# Get_In_Line_REV0.net
KiCad netlist of a schematic drawn in EAGLE
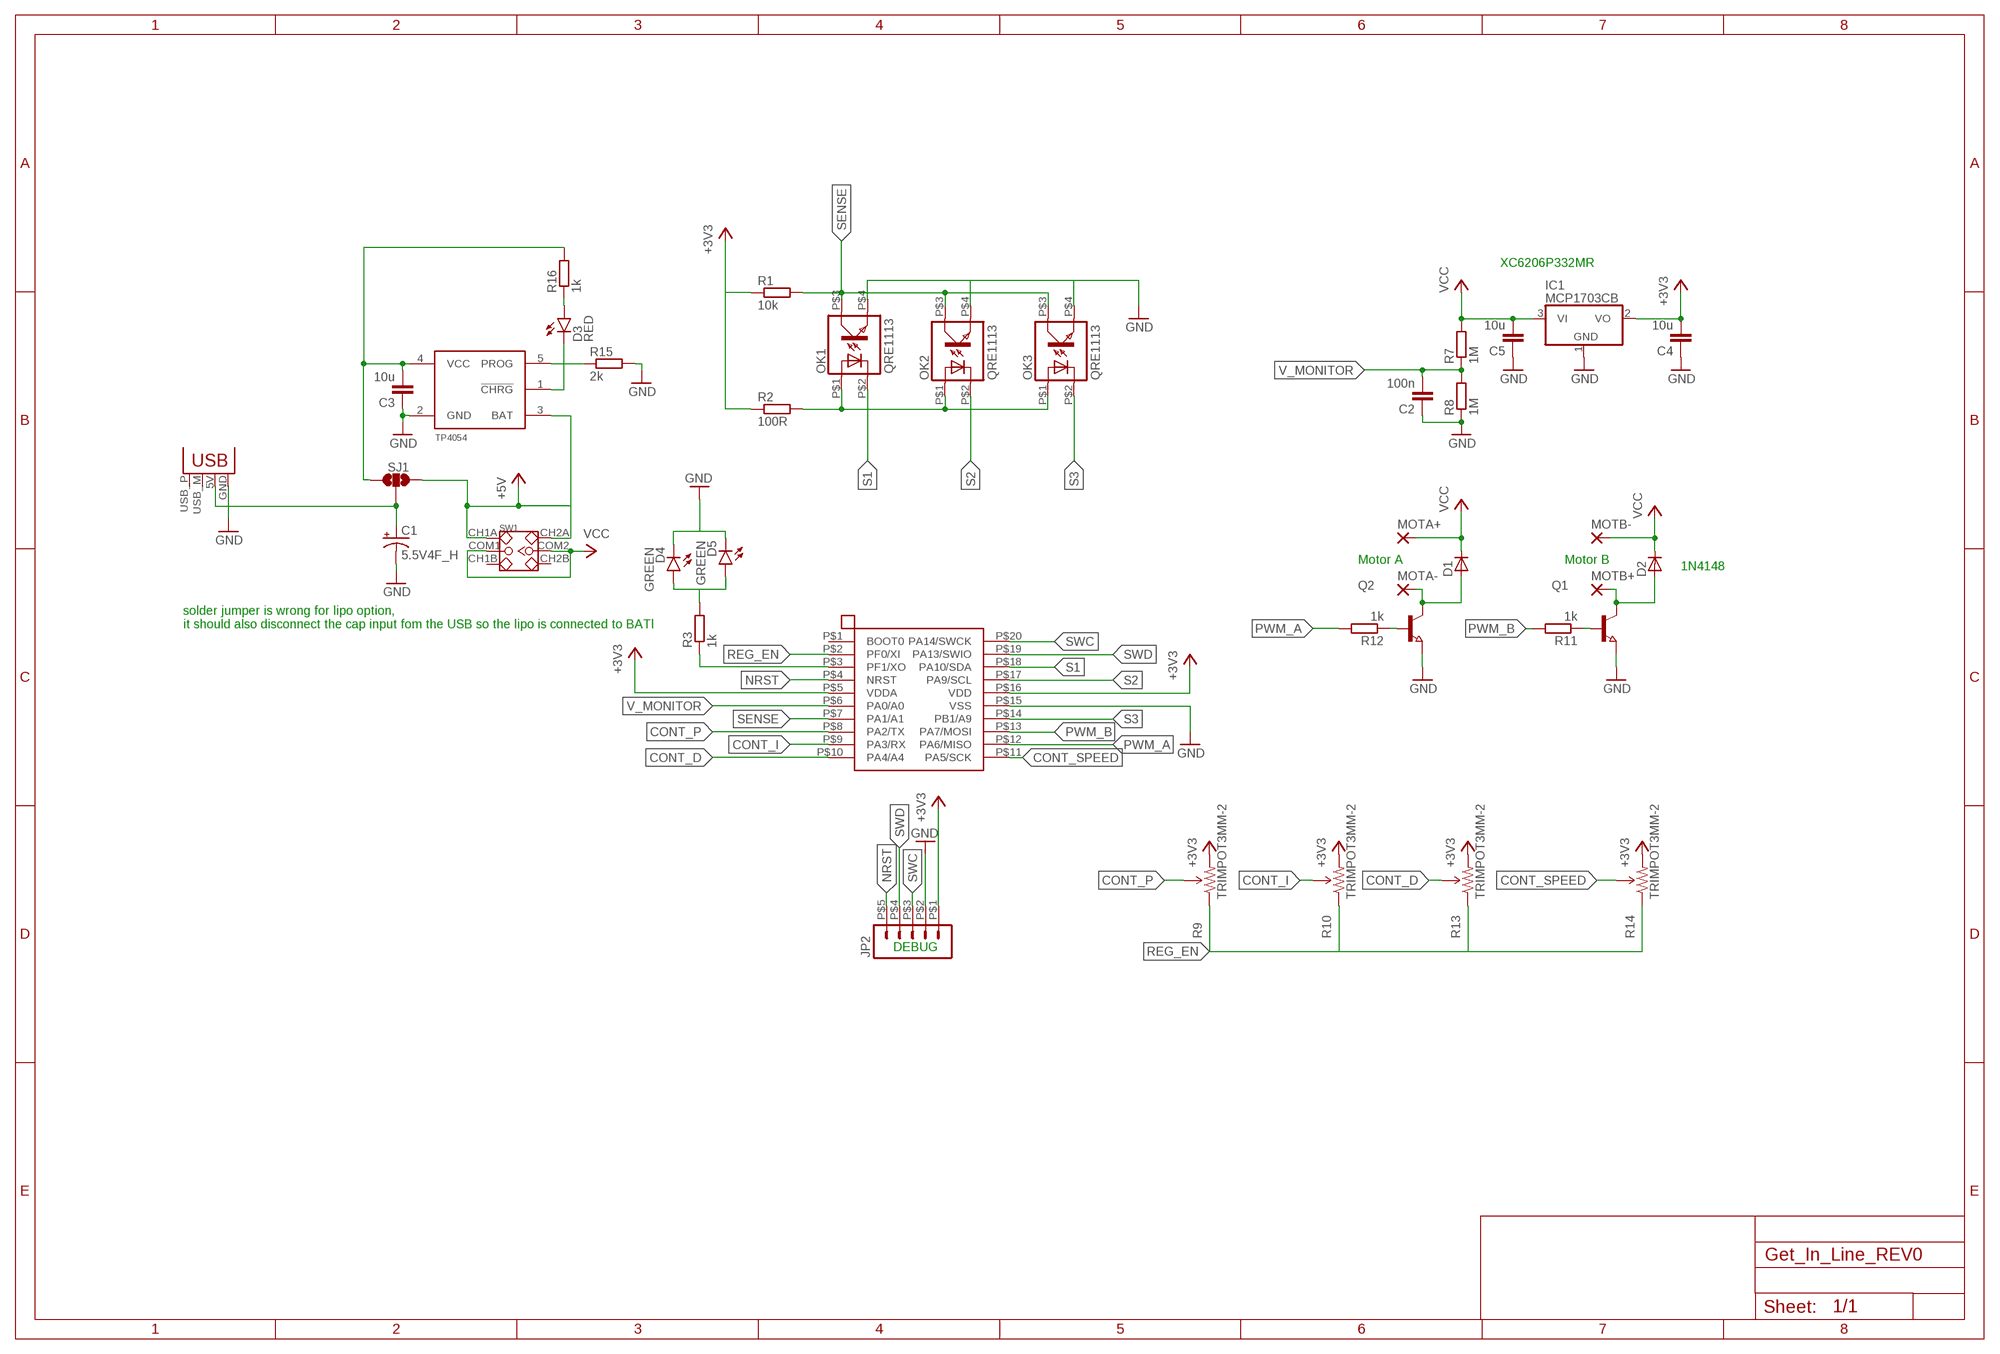
[diagram p0: schematic, sheet 1]

(export (version "E")
  (design (tool "Eeschema 10.0.6"))
  (components
    (comp (ref "C1")
      (value "5.5V4F_H")
      (footprint "eagle-import:5.5V4F_H")
      (libsource (lib "eagle-import") (part "5.5V4F_H"))
    )
    (comp (ref "C2")
      (value "100n")
      (footprint "eagle-import:C0805")
      (libsource (lib "eagle-import") (part "C-EUC0805"))
    )
    (comp (ref "C3")
      (value "10u")
      (footprint "eagle-import:C0805")
      (libsource (lib "eagle-import") (part "C-EUC0805"))
    )
    (comp (ref "C4")
      (value "10u")
      (footprint "eagle-import:C0805")
      (libsource (lib "eagle-import") (part "C-EUC0805"))
    )
    (comp (ref "C5")
      (value "10u")
      (footprint "eagle-import:C0805")
      (libsource (lib "eagle-import") (part "C-EUC0805"))
    )
    (comp (ref "D1")
      (value "D-SOD-80")
      (footprint "eagle-import:SOD80")
      (libsource (lib "eagle-import") (part "D-SOD-80"))
    )
    (comp (ref "D2")
      (value "D-SOD-80")
      (footprint "eagle-import:SOD80")
      (libsource (lib "eagle-import") (part "D-SOD-80"))
    )
    (comp (ref "D3")
      (value "RED")
      (footprint "eagle-import:LED-1206")
      (libsource (lib "eagle-import") (part "LED-RED1206"))
    )
    (comp (ref "D4")
      (value "GREEN")
      (footprint "eagle-import:LED-1206")
      (libsource (lib "eagle-import") (part "LED-GREENLARGE"))
    )
    (comp (ref "D5")
      (value "GREEN")
      (footprint "eagle-import:LED-1206")
      (libsource (lib "eagle-import") (part "LED-GREENLARGE"))
    )
    (comp (ref "IC1")
      (value "MCP1703CB")
      (footprint "eagle-import:SOT23")
      (libsource (lib "eagle-import") (part "MCP1703CB"))
    )
    (comp (ref "JP1")
      (value "USBPCB")
      (footprint "eagle-import:USB-A-PCB")
      (libsource (lib "eagle-import") (part "USBPCB"))
    )
    (comp (ref "JP2")
      (value "M05")
      (footprint "eagle-import:SMD_HEADER_5P")
      (libsource (lib "eagle-import") (part "M05"))
    )
    (comp (ref "MCU")
      (value "STM32F030F4P6")
      (footprint "eagle-import:TSSOP-20")
      (libsource (lib "eagle-import") (part "STM32F030F4P6"))
    )
    (comp (ref "MOTA+")
      (value "1,6/0,9")
      (footprint "eagle-import:1,6_0,9")
      (libsource (lib "eagle-import") (part "1,6/0,9"))
    )
    (comp (ref "MOTA-")
      (value "1,6/0,9")
      (footprint "eagle-import:1,6_0,9")
      (libsource (lib "eagle-import") (part "1,6/0,9"))
    )
    (comp (ref "MOTB+")
      (value "1,6/0,9")
      (footprint "eagle-import:1,6_0,9")
      (libsource (lib "eagle-import") (part "1,6/0,9"))
    )
    (comp (ref "MOTB-")
      (value "1,6/0,9")
      (footprint "eagle-import:1,6_0,9")
      (libsource (lib "eagle-import") (part "1,6/0,9"))
    )
    (comp (ref "OK1")
      (value "QRE1113")
      (footprint "eagle-import:DIL04")
      (libsource (lib "eagle-import") (part "QRE1113"))
    )
    (comp (ref "OK2")
      (value "QRE1113")
      (footprint "eagle-import:DIL04")
      (libsource (lib "eagle-import") (part "QRE1113"))
    )
    (comp (ref "OK3")
      (value "QRE1113")
      (footprint "eagle-import:DIL04")
      (libsource (lib "eagle-import") (part "QRE1113"))
    )
    (comp (ref "Q1")
      (value "NPN-TRANSISTOR_SOT23")
      (footprint "eagle-import:SOT23")
      (libsource (lib "eagle-import") (part "NPN-TRANSISTOR_SOT23"))
    )
    (comp (ref "Q2")
      (value "NPN-TRANSISTOR_SOT23")
      (footprint "eagle-import:SOT23")
      (libsource (lib "eagle-import") (part "NPN-TRANSISTOR_SOT23"))
    )
    (comp (ref "R1")
      (value "10k")
      (footprint "eagle-import:R0805")
      (libsource (lib "eagle-import") (part "R-EU_R0805"))
    )
    (comp (ref "R2")
      (value "100R")
      (footprint "eagle-import:R0805")
      (libsource (lib "eagle-import") (part "R-EU_R0805"))
    )
    (comp (ref "R3")
      (value "1k")
      (footprint "eagle-import:R0805")
      (libsource (lib "eagle-import") (part "R-EU_R0805"))
    )
    (comp (ref "R7")
      (value "1M")
      (footprint "eagle-import:R0805")
      (libsource (lib "eagle-import") (part "R-EU_R0805"))
    )
    (comp (ref "R8")
      (value "1M")
      (footprint "eagle-import:R0805")
      (libsource (lib "eagle-import") (part "R-EU_R0805"))
    )
    (comp (ref "R9")
      (value "TRIMPOT3MM-2")
      (footprint "eagle-import:TRIMPOT-3MM-2")
      (libsource (lib "eagle-import") (part "TRIMPOT3MM-2"))
    )
    (comp (ref "R10")
      (value "TRIMPOT3MM-2")
      (footprint "eagle-import:TRIMPOT-3MM-2")
      (libsource (lib "eagle-import") (part "TRIMPOT3MM-2"))
    )
    (comp (ref "R11")
      (value "1k")
      (footprint "eagle-import:R0805")
      (libsource (lib "eagle-import") (part "R-EU_R0805"))
    )
    (comp (ref "R12")
      (value "1k")
      (footprint "eagle-import:R0805")
      (libsource (lib "eagle-import") (part "R-EU_R0805"))
    )
    (comp (ref "R13")
      (value "TRIMPOT3MM-2")
      (footprint "eagle-import:TRIMPOT-3MM-2")
      (libsource (lib "eagle-import") (part "TRIMPOT3MM-2"))
    )
    (comp (ref "R14")
      (value "TRIMPOT3MM-2")
      (footprint "eagle-import:TRIMPOT-3MM-2")
      (libsource (lib "eagle-import") (part "TRIMPOT3MM-2"))
    )
    (comp (ref "R15")
      (value "2k")
      (footprint "eagle-import:R0805")
      (libsource (lib "eagle-import") (part "R-EU_R0805"))
    )
    (comp (ref "R16")
      (value "1k")
      (footprint "eagle-import:R0805")
      (libsource (lib "eagle-import") (part "R-EU_R0805"))
    )
    (comp (ref "SJ1")
      (value "JUMPER-PAD-3-NOFULL_BOX_SILK")
      (footprint "eagle-import:PAD-JUMPER-3-NO_YES_SILK_FULL_BOX")
      (libsource (lib "eagle-import") (part "JUMPER-PAD-3-NOFULL_BOX_SILK"))
    )
    (comp (ref "SW1")
      (value "DIP-TOGGLE-SWITCH-2CH-(2X3P-2.54)")
      (footprint "eagle-import:SW6-2.54-9.0X3.5X3.2+2.0MM")
      (fields (field (name "MPN") "MS-22D18 G2 ROHS"))
      (libsource (lib "eagle-import") (part "DIP-TOGGLE-SWITCH-2CH-(2X3P-2.54)"))
    )
    (comp (ref "U$1")
      (value "TP4054_LIPO_CHARGER")
      (footprint "eagle-import:SOT23-5")
      (libsource (lib "eagle-import") (part "TP4054_LIPO_CHARGER"))
    )
  )
  (nets
    (net (code "1") (name "+3V3") (class "Default")
      (node (ref "C4") (pin "2") (pinfunction "2_2") (pintype "passive"))
      (node (ref "IC1") (pin "2") (pinfunction "VO_2") (pintype "passive"))
      (node (ref "JP2") (pin "P$1") (pinfunction "1_P$1") (pintype "passive"))
      (node (ref "MCU") (pin "P$16") (pinfunction "VDD_P$16") (pintype "bidirectional"))
      (node (ref "MCU") (pin "P$5") (pinfunction "VDDA_P$5") (pintype "bidirectional"))
      (node (ref "R1") (pin "1") (pinfunction "1_1") (pintype "passive"))
      (node (ref "R10") (pin "3") (pinfunction "CW_3") (pintype "passive"))
      (node (ref "R13") (pin "3") (pinfunction "CW_3") (pintype "passive"))
      (node (ref "R14") (pin "3") (pinfunction "CW_3") (pintype "passive"))
      (node (ref "R2") (pin "1") (pinfunction "1_1") (pintype "passive"))
      (node (ref "R9") (pin "3") (pinfunction "CW_3") (pintype "passive"))
    )
    (net (code "2") (name "+5V") (class "Default")
      (node (ref "SJ1") (pin "3") (pinfunction "3_3") (pintype "passive"))
      (node (ref "SW1") (pin "CH1A") (pinfunction "CH1A_CH1A") (pintype "bidirectional"))
      (node (ref "SW1") (pin "CH2A") (pinfunction "CH2A_CH2A") (pintype "bidirectional"))
      (node (ref "U$1") (pin "3") (pinfunction "BAT_3") (pintype "bidirectional"))
    )
    (net (code "3") (name "CONT_D") (class "Default")
      (node (ref "MCU") (pin "P$10") (pinfunction "PA4/A4_P$10") (pintype "bidirectional"))
      (node (ref "R13") (pin "2") (pinfunction "WIPER_2") (pintype "passive"))
    )
    (net (code "4") (name "CONT_I") (class "Default")
      (node (ref "MCU") (pin "P$9") (pinfunction "PA3/RX_P$9") (pintype "bidirectional"))
      (node (ref "R10") (pin "2") (pinfunction "WIPER_2") (pintype "passive"))
    )
    (net (code "5") (name "CONT_P") (class "Default")
      (node (ref "MCU") (pin "P$8") (pinfunction "PA2/TX_P$8") (pintype "bidirectional"))
      (node (ref "R9") (pin "2") (pinfunction "WIPER_2") (pintype "passive"))
    )
    (net (code "6") (name "CONT_SPEED") (class "Default")
      (node (ref "MCU") (pin "P$11") (pinfunction "PA5/SCK_P$11") (pintype "bidirectional"))
      (node (ref "R14") (pin "2") (pinfunction "WIPER_2") (pintype "passive"))
    )
    (net (code "7") (name "GND") (class "Default")
      (node (ref "C1") (pin "P$2") (pinfunction "-_P$2") (pintype "passive"))
      (node (ref "C2") (pin "1") (pinfunction "1_1") (pintype "passive"))
      (node (ref "C3") (pin "1") (pinfunction "1_1") (pintype "passive"))
      (node (ref "C4") (pin "1") (pinfunction "1_1") (pintype "passive"))
      (node (ref "C5") (pin "1") (pinfunction "1_1") (pintype "passive"))
      (node (ref "D4") (pin "C") (pinfunction "C_C") (pintype "passive"))
      (node (ref "D5") (pin "C") (pinfunction "C_C") (pintype "passive"))
      (node (ref "IC1") (pin "1") (pinfunction "GND_1") (pintype "passive"))
      (node (ref "JP1") (pin "GND") (pinfunction "GND_GND") (pintype "bidirectional"))
      (node (ref "JP2") (pin "P$2") (pinfunction "2_P$2") (pintype "passive"))
      (node (ref "MCU") (pin "P$15") (pinfunction "VSS_P$15") (pintype "bidirectional"))
      (node (ref "OK1") (pin "P$4") (pinfunction "EMIT_P$4") (pintype "passive"))
      (node (ref "OK2") (pin "P$4") (pinfunction "EMIT_P$4") (pintype "passive"))
      (node (ref "OK3") (pin "P$4") (pinfunction "EMIT_P$4") (pintype "passive"))
      (node (ref "Q1") (pin "2") (pinfunction "E_2") (pintype "passive"))
      (node (ref "Q2") (pin "2") (pinfunction "E_2") (pintype "passive"))
      (node (ref "R15") (pin "2") (pinfunction "2_2") (pintype "passive"))
      (node (ref "R8") (pin "1") (pinfunction "1_1") (pintype "passive"))
      (node (ref "U$1") (pin "2") (pinfunction "GND_2") (pintype "bidirectional"))
    )
    (net (code "8") (name "NRST") (class "Default")
      (node (ref "JP2") (pin "P$5") (pinfunction "5_P$5") (pintype "passive"))
      (node (ref "MCU") (pin "P$4") (pinfunction "NRST_P$4") (pintype "bidirectional"))
    )
    (net (code "9") (name "Net-(C1-+)") (class "Default")
      (node (ref "C1") (pin "P$1") (pinfunction "+_P$1") (pintype "passive"))
      (node (ref "JP1") (pin "5V") (pinfunction "VBUS_5V") (pintype "bidirectional"))
      (node (ref "SJ1") (pin "2") (pinfunction "2_2") (pintype "passive"))
    )
    (net (code "10") (name "Net-(D1-A)") (class "Default")
      (node (ref "D1") (pin "2") (pinfunction "A_2") (pintype "passive"))
      (node (ref "MOTA-") (pin "1") (pinfunction "P_1") (pintype "passive"))
      (node (ref "Q2") (pin "3") (pinfunction "C_3") (pintype "passive"))
    )
    (net (code "11") (name "Net-(D2-A)") (class "Default")
      (node (ref "D2") (pin "2") (pinfunction "A_2") (pintype "passive"))
      (node (ref "MOTB+") (pin "1") (pinfunction "P_1") (pintype "passive"))
      (node (ref "Q1") (pin "3") (pinfunction "C_3") (pintype "passive"))
    )
    (net (code "12") (name "Net-(D3-PadA)") (class "Default")
      (node (ref "D3") (pin "A") (pinfunction "A_A") (pintype "passive"))
      (node (ref "R16") (pin "1") (pinfunction "1_1") (pintype "passive"))
    )
    (net (code "13") (name "Net-(D4-PadA)") (class "Default")
      (node (ref "D4") (pin "A") (pinfunction "A_A") (pintype "passive"))
      (node (ref "D5") (pin "A") (pinfunction "A_A") (pintype "passive"))
      (node (ref "R3") (pin "2") (pinfunction "2_2") (pintype "passive"))
    )
    (net (code "14") (name "Net-(MCU-PF1{slash}XO)") (class "Default")
      (node (ref "MCU") (pin "P$3") (pinfunction "PF1/XO_P$3") (pintype "bidirectional"))
      (node (ref "R3") (pin "1") (pinfunction "1_1") (pintype "passive"))
    )
    (net (code "15") (name "Net-(OK1-A)") (class "Default")
      (node (ref "OK1") (pin "P$1") (pinfunction "A_P$1") (pintype "passive"))
      (node (ref "OK2") (pin "P$1") (pinfunction "A_P$1") (pintype "passive"))
      (node (ref "OK3") (pin "P$1") (pinfunction "A_P$1") (pintype "passive"))
      (node (ref "R2") (pin "2") (pinfunction "2_2") (pintype "passive"))
    )
    (net (code "16") (name "Net-(Q1-B)") (class "Default")
      (node (ref "Q1") (pin "1") (pinfunction "B_1") (pintype "passive"))
      (node (ref "R11") (pin "1") (pinfunction "1_1") (pintype "passive"))
    )
    (net (code "17") (name "Net-(Q2-B)") (class "Default")
      (node (ref "Q2") (pin "1") (pinfunction "B_1") (pintype "passive"))
      (node (ref "R12") (pin "1") (pinfunction "1_1") (pintype "passive"))
    )
    (net (code "18") (name "Net-(U$1-PROG)") (class "Default")
      (node (ref "R15") (pin "1") (pinfunction "1_1") (pintype "passive"))
      (node (ref "U$1") (pin "5") (pinfunction "PROG_5") (pintype "bidirectional"))
    )
    (net (code "19") (name "Net-(U$1-VCC)") (class "Default")
      (node (ref "C3") (pin "2") (pinfunction "2_2") (pintype "passive"))
      (node (ref "R16") (pin "2") (pinfunction "2_2") (pintype "passive"))
      (node (ref "SJ1") (pin "1") (pinfunction "1_1") (pintype "passive"))
      (node (ref "U$1") (pin "4") (pinfunction "VCC_4") (pintype "bidirectional"))
    )
    (net (code "20") (name "Net-(U$1-~{CHRG})") (class "Default")
      (node (ref "D3") (pin "C") (pinfunction "C_C") (pintype "passive"))
      (node (ref "U$1") (pin "1") (pinfunction "~{CHRG}_1") (pintype "bidirectional"))
    )
    (net (code "21") (name "PWM_A") (class "Default")
      (node (ref "MCU") (pin "P$12") (pinfunction "PA6/MISO_P$12") (pintype "bidirectional"))
      (node (ref "R12") (pin "2") (pinfunction "2_2") (pintype "passive"))
    )
    (net (code "22") (name "PWM_B") (class "Default")
      (node (ref "MCU") (pin "P$13") (pinfunction "PA7/MOSI_P$13") (pintype "bidirectional"))
      (node (ref "R11") (pin "2") (pinfunction "2_2") (pintype "passive"))
    )
    (net (code "23") (name "REG_EN") (class "Default")
      (node (ref "MCU") (pin "P$2") (pinfunction "PF0/XI_P$2") (pintype "bidirectional"))
      (node (ref "R10") (pin "1") (pinfunction "CCW_1") (pintype "passive"))
      (node (ref "R13") (pin "1") (pinfunction "CCW_1") (pintype "passive"))
      (node (ref "R14") (pin "1") (pinfunction "CCW_1") (pintype "passive"))
      (node (ref "R9") (pin "1") (pinfunction "CCW_1") (pintype "passive"))
    )
    (net (code "24") (name "S1") (class "Default")
      (node (ref "MCU") (pin "P$18") (pinfunction "PA10/SDA_P$18") (pintype "bidirectional"))
      (node (ref "OK1") (pin "P$2") (pinfunction "C_P$2") (pintype "passive"))
    )
    (net (code "25") (name "S2") (class "Default")
      (node (ref "MCU") (pin "P$17") (pinfunction "PA9/SCL_P$17") (pintype "bidirectional"))
      (node (ref "OK2") (pin "P$2") (pinfunction "C_P$2") (pintype "passive"))
    )
    (net (code "26") (name "S3") (class "Default")
      (node (ref "MCU") (pin "P$14") (pinfunction "PB1/A9_P$14") (pintype "bidirectional"))
      (node (ref "OK3") (pin "P$2") (pinfunction "C_P$2") (pintype "passive"))
    )
    (net (code "27") (name "SENSE") (class "Default")
      (node (ref "MCU") (pin "P$7") (pinfunction "PA1/A1_P$7") (pintype "bidirectional"))
      (node (ref "OK1") (pin "P$3") (pinfunction "COL_P$3") (pintype "passive"))
      (node (ref "OK2") (pin "P$3") (pinfunction "COL_P$3") (pintype "passive"))
      (node (ref "OK3") (pin "P$3") (pinfunction "COL_P$3") (pintype "passive"))
      (node (ref "R1") (pin "2") (pinfunction "2_2") (pintype "passive"))
    )
    (net (code "28") (name "SWC") (class "Default")
      (node (ref "JP2") (pin "P$3") (pinfunction "3_P$3") (pintype "passive"))
      (node (ref "MCU") (pin "P$20") (pinfunction "PA14/SWCK_P$20") (pintype "bidirectional"))
    )
    (net (code "29") (name "SWD") (class "Default")
      (node (ref "JP2") (pin "P$4") (pinfunction "4_P$4") (pintype "passive"))
      (node (ref "MCU") (pin "P$19") (pinfunction "PA13/SWIO_P$19") (pintype "bidirectional"))
    )
    (net (code "30") (name "VCC") (class "Default")
      (node (ref "C5") (pin "2") (pinfunction "2_2") (pintype "passive"))
      (node (ref "D1") (pin "1") (pinfunction "C_1") (pintype "passive"))
      (node (ref "D2") (pin "1") (pinfunction "C_1") (pintype "passive"))
      (node (ref "IC1") (pin "3") (pinfunction "VI_3") (pintype "input"))
      (node (ref "MOTA+") (pin "1") (pinfunction "P_1") (pintype "passive"))
      (node (ref "MOTB-") (pin "1") (pinfunction "P_1") (pintype "passive"))
      (node (ref "R7") (pin "2") (pinfunction "2_2") (pintype "passive"))
      (node (ref "SW1") (pin "COM1") (pinfunction "COM1_COM1") (pintype "bidirectional"))
      (node (ref "SW1") (pin "COM2") (pinfunction "COM2_COM2") (pintype "bidirectional"))
    )
    (net (code "31") (name "V_MONITOR") (class "Default")
      (node (ref "C2") (pin "2") (pinfunction "2_2") (pintype "passive"))
      (node (ref "MCU") (pin "P$6") (pinfunction "PA0/A0_P$6") (pintype "bidirectional"))
      (node (ref "R7") (pin "1") (pinfunction "1_1") (pintype "passive"))
      (node (ref "R8") (pin "2") (pinfunction "2_2") (pintype "passive"))
    )
    (net (code "32") (name "unconnected-(JP1-D+-PadUSB_P)") (class "Default")
      (node (ref "JP1") (pin "USB_P") (pinfunction "D+_USB_P") (pintype "bidirectional"))
    )
    (net (code "33") (name "unconnected-(JP1-D--PadUSB_M)") (class "Default")
      (node (ref "JP1") (pin "USB_M") (pinfunction "D-_USB_M") (pintype "bidirectional"))
    )
    (net (code "34") (name "unconnected-(MCU-BOOT0-PadP$1)") (class "Default")
      (node (ref "MCU") (pin "P$1") (pinfunction "BOOT0_P$1") (pintype "bidirectional"))
    )
    (net (code "35") (name "unconnected-(SW1-PadCH1B)") (class "Default")
      (node (ref "SW1") (pin "CH1B") (pinfunction "CH1B_CH1B") (pintype "bidirectional"))
    )
    (net (code "36") (name "unconnected-(SW1-PadCH2B)") (class "Default")
      (node (ref "SW1") (pin "CH2B") (pinfunction "CH2B_CH2B") (pintype "bidirectional"))
    )
  )
)
